# sch.net
KiCad netlist of a schematic drawn in Altium Designer
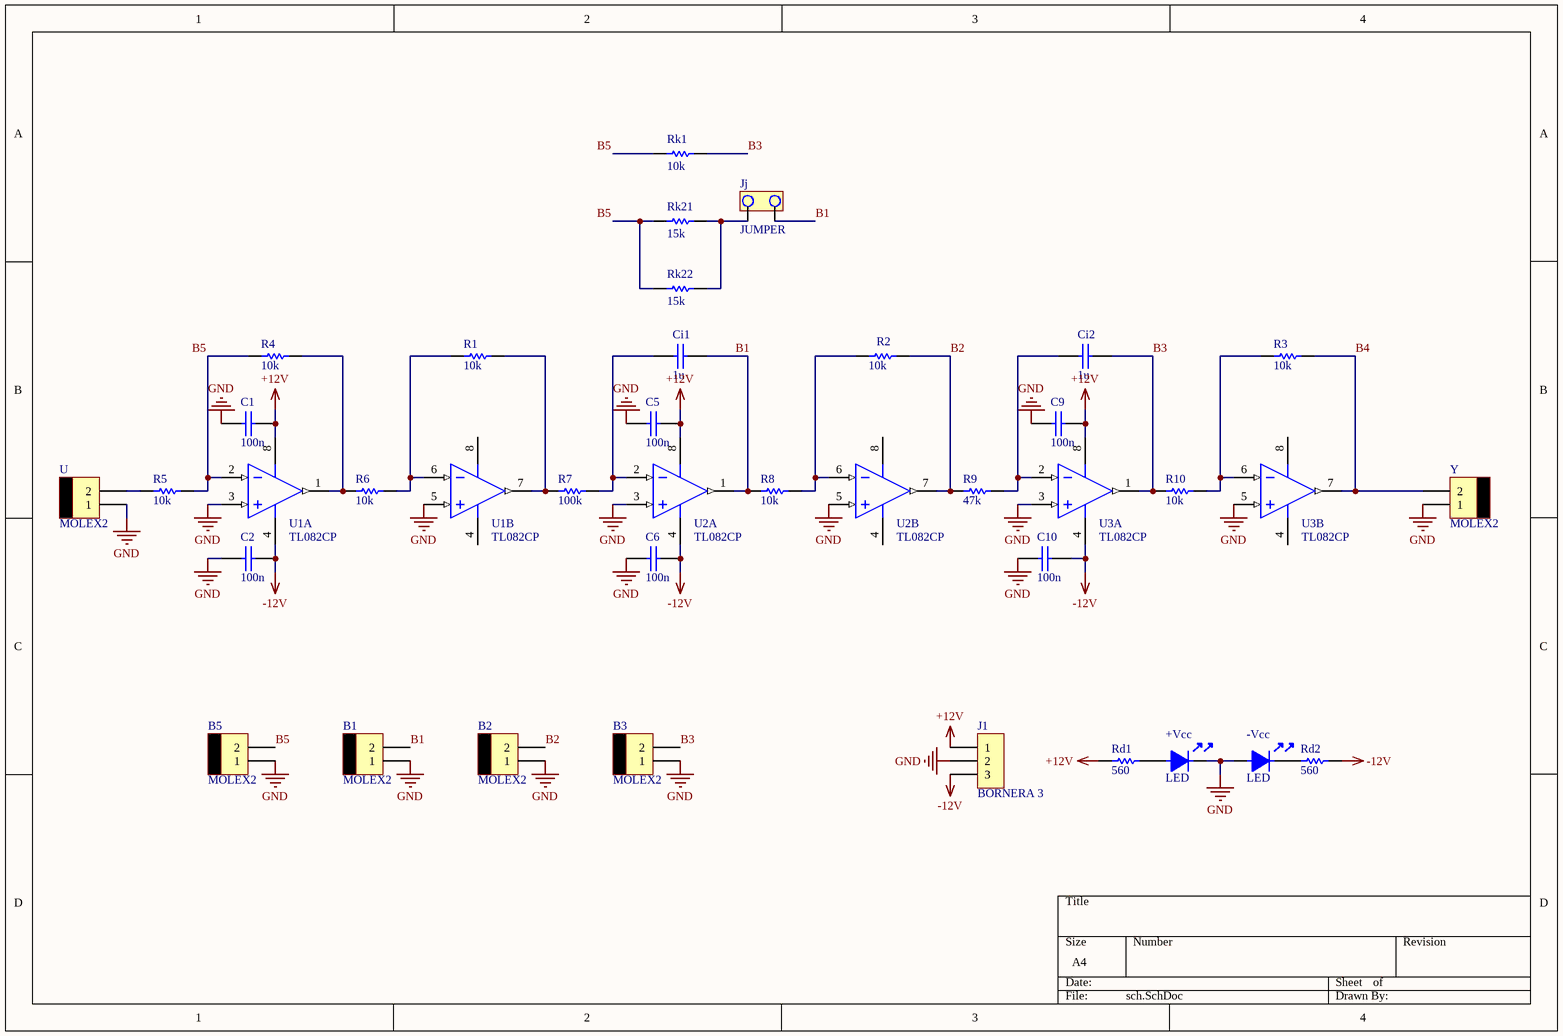
[diagram p0: sch.SchDoc]

(export (version "E")
  (design (tool "Eeschema 10.0.6"))
  (components
    (comp (ref "+Vcc") (value "LED") (footprint "LED3") (libsource (lib "LIBEBAL") (part "LED")))
    (comp (ref "-Vcc") (value "LED") (footprint "LED3") (libsource (lib "LIBEBAL") (part "LED")))
    (comp (ref "B1") (value "MOLEX2") (footprint "MOLEX2") (libsource (lib "LIBEBAL") (part "MOLEX2")))
    (comp (ref "B2") (value "MOLEX2") (footprint "MOLEX2") (libsource (lib "LIBEBAL") (part "MOLEX2")))
    (comp (ref "B3") (value "MOLEX2") (footprint "MOLEX2") (libsource (lib "LIBEBAL") (part "MOLEX2")))
    (comp (ref "B5") (value "MOLEX2") (footprint "MOLEX2") (libsource (lib "LIBEBAL") (part "MOLEX2")))
    (comp (ref "C1") (value "100n") (footprint "CAP200") (libsource (lib "LIBEBAL") (part "CAP")))
    (comp (ref "C2") (value "100n") (footprint "CAP100") (libsource (lib "LIBEBAL") (part "CAP")))
    (comp (ref "C5") (value "100n") (footprint "CAP200") (libsource (lib "LIBEBAL") (part "CAP")))
    (comp (ref "C6") (value "100n") (footprint "CAP100") (libsource (lib "LIBEBAL") (part "CAP")))
    (comp (ref "C9") (value "100n") (footprint "CAP200") (libsource (lib "LIBEBAL") (part "CAP")))
    (comp (ref "C10") (value "100n") (footprint "CAP100") (libsource (lib "LIBEBAL") (part "CAP")))
    (comp (ref "Ci1") (value "1u") (footprint "CAP100") (libsource (lib "LIBEBAL") (part "CAP")))
    (comp (ref "Ci2") (value "1u") (footprint "CAP100") (libsource (lib "LIBEBAL") (part "CAP")))
    (comp (ref "J1")
      (value "BORNERA 3")
      (footprint "BORNERA3")
      (libsource (lib "LIBEBAL") (part "BORNERA 3"))
    )
    (comp (ref "Jj") (value "JUMPER") (footprint "JUMPER2") (libsource (lib "LIBEBAL") (part "JUMPER")))
    (comp (ref "R1") (value "10k") (footprint "RES300") (libsource (lib "LIBEBAL") (part "RES")))
    (comp (ref "R2") (value "10k") (footprint "RES300") (libsource (lib "LIBEBAL") (part "RES")))
    (comp (ref "R3") (value "10k") (footprint "RES300") (libsource (lib "LIBEBAL") (part "RES")))
    (comp (ref "R4") (value "10k") (footprint "RES300") (libsource (lib "LIBEBAL") (part "RES")))
    (comp (ref "R5") (value "10k") (footprint "RES300") (libsource (lib "LIBEBAL") (part "RES")))
    (comp (ref "R6") (value "10k") (footprint "RES300") (libsource (lib "LIBEBAL") (part "RES")))
    (comp (ref "R7") (value "100k") (footprint "RES300") (libsource (lib "LIBEBAL") (part "RES")))
    (comp (ref "R8") (value "10k") (footprint "RES300") (libsource (lib "LIBEBAL") (part "RES")))
    (comp (ref "R9") (value "47k") (footprint "RES300") (libsource (lib "LIBEBAL") (part "RES")))
    (comp (ref "R10") (value "10k") (footprint "RES300") (libsource (lib "LIBEBAL") (part "RES")))
    (comp (ref "Rd1") (value "560") (footprint "RES300") (libsource (lib "LIBEBAL") (part "RES")))
    (comp (ref "Rd2") (value "560") (footprint "RES300") (libsource (lib "LIBEBAL") (part "RES")))
    (comp (ref "Rk1") (value "10k") (footprint "RES300") (libsource (lib "LIBEBAL") (part "RES")))
    (comp (ref "Rk21") (value "15k") (footprint "RES300") (libsource (lib "LIBEBAL") (part "RES")))
    (comp (ref "Rk22") (value "15k") (footprint "RES400") (libsource (lib "LIBEBAL") (part "RES")))
    (comp (ref "U") (value "MOLEX2") (footprint "MOLEX2") (libsource (lib "LIBEBAL") (part "MOLEX2")))
    (comp (ref "U1")
      (value "TL082CP")
      (footprint "P0008A")
      (description "JFET-Input Operational Amplifier, 7 to 36 V, 0 to 70 degC, 8-pin DIP (P8), Pb-Free (RoHS)")
      (fields (field (name "MANUFACTURER") "Texas Instruments"))
      (libsource (lib "Altium Content Vault") (part "TI-AMP-D6-2-8_D"))
    )
    (comp (ref "U2")
      (value "TL082CP")
      (footprint "P0008A")
      (description "JFET-Input Operational Amplifier, 7 to 36 V, 0 to 70 degC, 8-pin DIP (P8), Pb-Free (RoHS)")
      (fields (field (name "MANUFACTURER") "Texas Instruments"))
      (libsource (lib "Altium Content Vault") (part "TI-AMP-D6-2-8_D"))
    )
    (comp (ref "U3")
      (value "TL082CP")
      (footprint "P0008A")
      (description "JFET-Input Operational Amplifier, 7 to 36 V, 0 to 70 degC, 8-pin DIP (P8), Pb-Free (RoHS)")
      (fields (field (name "MANUFACTURER") "Texas Instruments"))
      (libsource (lib "Altium Content Vault") (part "TI-AMP-D6-2-8_D"))
    )
    (comp (ref "Y") (value "MOLEX2") (footprint "MOLEX2") (libsource (lib "") (part "MOLEX2_1")))
  )
  (nets
    (net (code "1") (name "+12V") (class "Default")
      (node (ref "C1") (pin "1") (pinfunction "1_1") (pintype "passive"))
      (node (ref "C5") (pin "1") (pinfunction "1_1") (pintype "passive"))
      (node (ref "C9") (pin "1") (pinfunction "1_1") (pintype "passive"))
      (node (ref "J1") (pin "1") (pinfunction "1_1") (pintype "passive"))
      (node (ref "Rd1") (pin "1") (pinfunction "1_1") (pintype "passive"))
      (node (ref "U1") (pin "8") (pinfunction "VCC+_8") (pintype "power_in"))
      (node (ref "U2") (pin "8") (pinfunction "VCC+_8") (pintype "power_in"))
      (node (ref "U3") (pin "8") (pinfunction "VCC+_8") (pintype "power_in"))
    )
    (net (code "2") (name "-12V") (class "Default")
      (node (ref "C10") (pin "1") (pinfunction "1_1") (pintype "passive"))
      (node (ref "C2") (pin "1") (pinfunction "1_1") (pintype "passive"))
      (node (ref "C6") (pin "1") (pinfunction "1_1") (pintype "passive"))
      (node (ref "J1") (pin "3") (pinfunction "3_3") (pintype "passive"))
      (node (ref "Rd2") (pin "2") (pinfunction "2_2") (pintype "passive"))
      (node (ref "U1") (pin "4") (pinfunction "VCC-_4") (pintype "power_in"))
      (node (ref "U2") (pin "4") (pinfunction "VCC-_4") (pintype "power_in"))
      (node (ref "U3") (pin "4") (pinfunction "VCC-_4") (pintype "power_in"))
    )
    (net (code "3") (name "/B1") (class "Default")
      (node (ref "B1") (pin "2") (pinfunction "2_2") (pintype "passive"))
      (node (ref "Ci1") (pin "1") (pinfunction "1_1") (pintype "passive"))
      (node (ref "Jj") (pin "1") (pinfunction "1_1") (pintype "passive"))
      (node (ref "R8") (pin "1") (pinfunction "1_1") (pintype "passive"))
      (node (ref "U2") (pin "1") (pinfunction "OUT1_1") (pintype "output"))
    )
    (net (code "4") (name "/B2") (class "Default")
      (node (ref "B2") (pin "2") (pinfunction "2_2") (pintype "passive"))
      (node (ref "R2") (pin "2") (pinfunction "2_2") (pintype "passive"))
      (node (ref "R9") (pin "1") (pinfunction "1_1") (pintype "passive"))
      (node (ref "U2") (pin "7") (pinfunction "OUT2_7") (pintype "output"))
    )
    (net (code "5") (name "/B3") (class "Default")
      (node (ref "B3") (pin "2") (pinfunction "2_2") (pintype "passive"))
      (node (ref "Ci2") (pin "1") (pinfunction "1_1") (pintype "passive"))
      (node (ref "R10") (pin "1") (pinfunction "1_1") (pintype "passive"))
      (node (ref "Rk1") (pin "2") (pinfunction "2_2") (pintype "passive"))
      (node (ref "U3") (pin "1") (pinfunction "OUT1_1") (pintype "output"))
    )
    (net (code "6") (name "/B4") (class "Default")
      (node (ref "R3") (pin "2") (pinfunction "2_2") (pintype "passive"))
      (node (ref "U3") (pin "7") (pinfunction "OUT2_7") (pintype "output"))
      (node (ref "Y") (pin "2") (pinfunction "2_2") (pintype "passive"))
    )
    (net (code "7") (name "/B5") (class "Default")
      (node (ref "B5") (pin "2") (pinfunction "2_2") (pintype "passive"))
      (node (ref "R4") (pin "1") (pinfunction "1_1") (pintype "passive"))
      (node (ref "R5") (pin "2") (pinfunction "2_2") (pintype "passive"))
      (node (ref "Rk1") (pin "1") (pinfunction "1_1") (pintype "passive"))
      (node (ref "Rk21") (pin "1") (pinfunction "1_1") (pintype "passive"))
      (node (ref "Rk22") (pin "1") (pinfunction "1_1") (pintype "passive"))
      (node (ref "U1") (pin "2") (pinfunction "IN1-_2") (pintype "input"))
    )
    (net (code "8") (name "GND") (class "Default")
      (node (ref "+Vcc") (pin "2") (pinfunction "2_2") (pintype "passive"))
      (node (ref "-Vcc") (pin "1") (pinfunction "1_1") (pintype "passive"))
      (node (ref "B1") (pin "1") (pinfunction "1_1") (pintype "passive"))
      (node (ref "B2") (pin "1") (pinfunction "1_1") (pintype "passive"))
      (node (ref "B3") (pin "1") (pinfunction "1_1") (pintype "passive"))
      (node (ref "B5") (pin "1") (pinfunction "1_1") (pintype "passive"))
      (node (ref "C1") (pin "2") (pinfunction "2_2") (pintype "passive"))
      (node (ref "C10") (pin "2") (pinfunction "2_2") (pintype "passive"))
      (node (ref "C2") (pin "2") (pinfunction "2_2") (pintype "passive"))
      (node (ref "C5") (pin "2") (pinfunction "2_2") (pintype "passive"))
      (node (ref "C6") (pin "2") (pinfunction "2_2") (pintype "passive"))
      (node (ref "C9") (pin "2") (pinfunction "2_2") (pintype "passive"))
      (node (ref "J1") (pin "2") (pinfunction "2_2") (pintype "passive"))
      (node (ref "U") (pin "1") (pinfunction "1_1") (pintype "passive"))
      (node (ref "U1") (pin "3") (pinfunction "IN1+_3") (pintype "input"))
      (node (ref "U1") (pin "5") (pinfunction "IN2+_5") (pintype "input"))
      (node (ref "U2") (pin "3") (pinfunction "IN1+_3") (pintype "input"))
      (node (ref "U2") (pin "5") (pinfunction "IN2+_5") (pintype "input"))
      (node (ref "U3") (pin "3") (pinfunction "IN1+_3") (pintype "input"))
      (node (ref "U3") (pin "5") (pinfunction "IN2+_5") (pintype "input"))
      (node (ref "Y") (pin "1") (pinfunction "1_1") (pintype "passive"))
    )
    (net (code "9") (name "Net-(+Vcc-Pad1)") (class "Default")
      (node (ref "+Vcc") (pin "1") (pinfunction "1_1") (pintype "passive"))
      (node (ref "Rd1") (pin "2") (pinfunction "2_2") (pintype "passive"))
    )
    (net (code "10") (name "Net-(-Vcc-Pad2)") (class "Default")
      (node (ref "-Vcc") (pin "2") (pinfunction "2_2") (pintype "passive"))
      (node (ref "Rd2") (pin "1") (pinfunction "1_1") (pintype "passive"))
    )
    (net (code "11") (name "Net-(Jj-Pad2)") (class "Default")
      (node (ref "Jj") (pin "2") (pinfunction "2_2") (pintype "passive"))
      (node (ref "Rk21") (pin "2") (pinfunction "2_2") (pintype "passive"))
      (node (ref "Rk22") (pin "2") (pinfunction "2_2") (pintype "passive"))
    )
    (net (code "12") (name "Net-(R5-Pad1)") (class "Default")
      (node (ref "R5") (pin "1") (pinfunction "1_1") (pintype "passive"))
      (node (ref "U") (pin "2") (pinfunction "2_2") (pintype "passive"))
    )
    (net (code "13") (name "Net-(U1A-OUT1)") (class "Default")
      (node (ref "R4") (pin "2") (pinfunction "2_2") (pintype "passive"))
      (node (ref "R6") (pin "1") (pinfunction "1_1") (pintype "passive"))
      (node (ref "U1") (pin "1") (pinfunction "OUT1_1") (pintype "output"))
    )
    (net (code "14") (name "Net-(U1B-IN2-)") (class "Default")
      (node (ref "R1") (pin "1") (pinfunction "1_1") (pintype "passive"))
      (node (ref "R6") (pin "2") (pinfunction "2_2") (pintype "passive"))
      (node (ref "U1") (pin "6") (pinfunction "IN2-_6") (pintype "input"))
    )
    (net (code "15") (name "Net-(U1B-OUT2)") (class "Default")
      (node (ref "R1") (pin "2") (pinfunction "2_2") (pintype "passive"))
      (node (ref "R7") (pin "1") (pinfunction "1_1") (pintype "passive"))
      (node (ref "U1") (pin "7") (pinfunction "OUT2_7") (pintype "output"))
    )
    (net (code "16") (name "Net-(U2A-IN1-)") (class "Default")
      (node (ref "Ci1") (pin "2") (pinfunction "2_2") (pintype "passive"))
      (node (ref "R7") (pin "2") (pinfunction "2_2") (pintype "passive"))
      (node (ref "U2") (pin "2") (pinfunction "IN1-_2") (pintype "input"))
    )
    (net (code "17") (name "Net-(U2B-IN2-)") (class "Default")
      (node (ref "R2") (pin "1") (pinfunction "1_1") (pintype "passive"))
      (node (ref "R8") (pin "2") (pinfunction "2_2") (pintype "passive"))
      (node (ref "U2") (pin "6") (pinfunction "IN2-_6") (pintype "input"))
    )
    (net (code "18") (name "Net-(U3A-IN1-)") (class "Default")
      (node (ref "Ci2") (pin "2") (pinfunction "2_2") (pintype "passive"))
      (node (ref "R9") (pin "2") (pinfunction "2_2") (pintype "passive"))
      (node (ref "U3") (pin "2") (pinfunction "IN1-_2") (pintype "input"))
    )
    (net (code "19") (name "Net-(U3B-IN2-)") (class "Default")
      (node (ref "R10") (pin "2") (pinfunction "2_2") (pintype "passive"))
      (node (ref "R3") (pin "1") (pinfunction "1_1") (pintype "passive"))
      (node (ref "U3") (pin "6") (pinfunction "IN2-_6") (pintype "input"))
    )
    (net (code "20") (name "unconnected-(U1B-VCC+-Pad8)") (class "Default")
      (node (ref "U1") (pin "8") (pinfunction "VCC+_8") (pintype "power_in"))
    )
    (net (code "21") (name "unconnected-(U1B-VCC--Pad4)") (class "Default")
      (node (ref "U1") (pin "4") (pinfunction "VCC-_4") (pintype "power_in"))
    )
    (net (code "22") (name "unconnected-(U2B-VCC+-Pad8)") (class "Default")
      (node (ref "U2") (pin "8") (pinfunction "VCC+_8") (pintype "power_in"))
    )
    (net (code "23") (name "unconnected-(U2B-VCC--Pad4)") (class "Default")
      (node (ref "U2") (pin "4") (pinfunction "VCC-_4") (pintype "power_in"))
    )
    (net (code "24") (name "unconnected-(U3B-VCC+-Pad8)") (class "Default")
      (node (ref "U3") (pin "8") (pinfunction "VCC+_8") (pintype "power_in"))
    )
    (net (code "25") (name "unconnected-(U3B-VCC--Pad4)") (class "Default")
      (node (ref "U3") (pin "4") (pinfunction "VCC-_4") (pintype "power_in"))
    )
  )
)
